# GaggiaBoard_V3.net
KiCad netlist of a schematic drawn in EAGLE
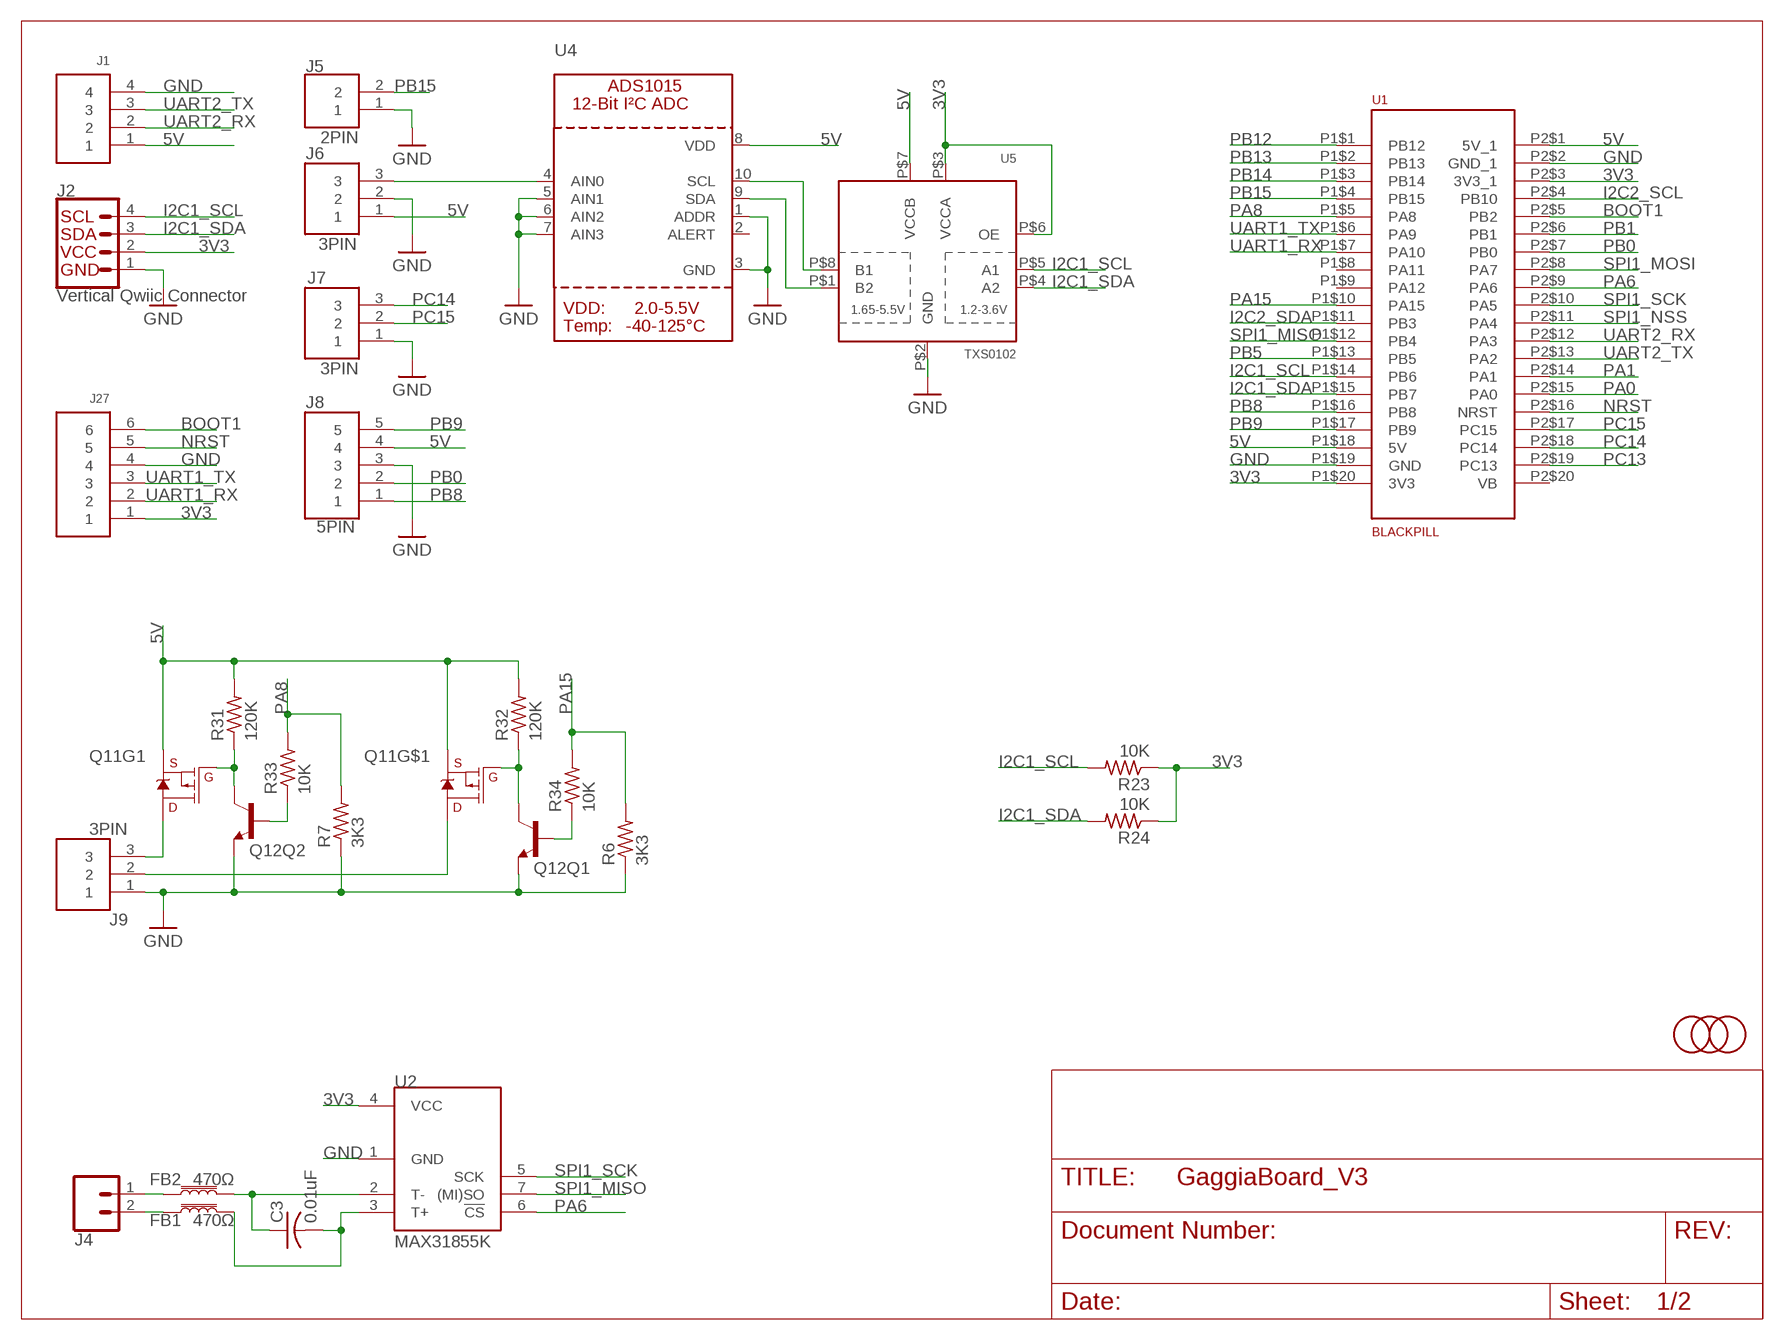
[diagram p0: schematic, sheet 1]
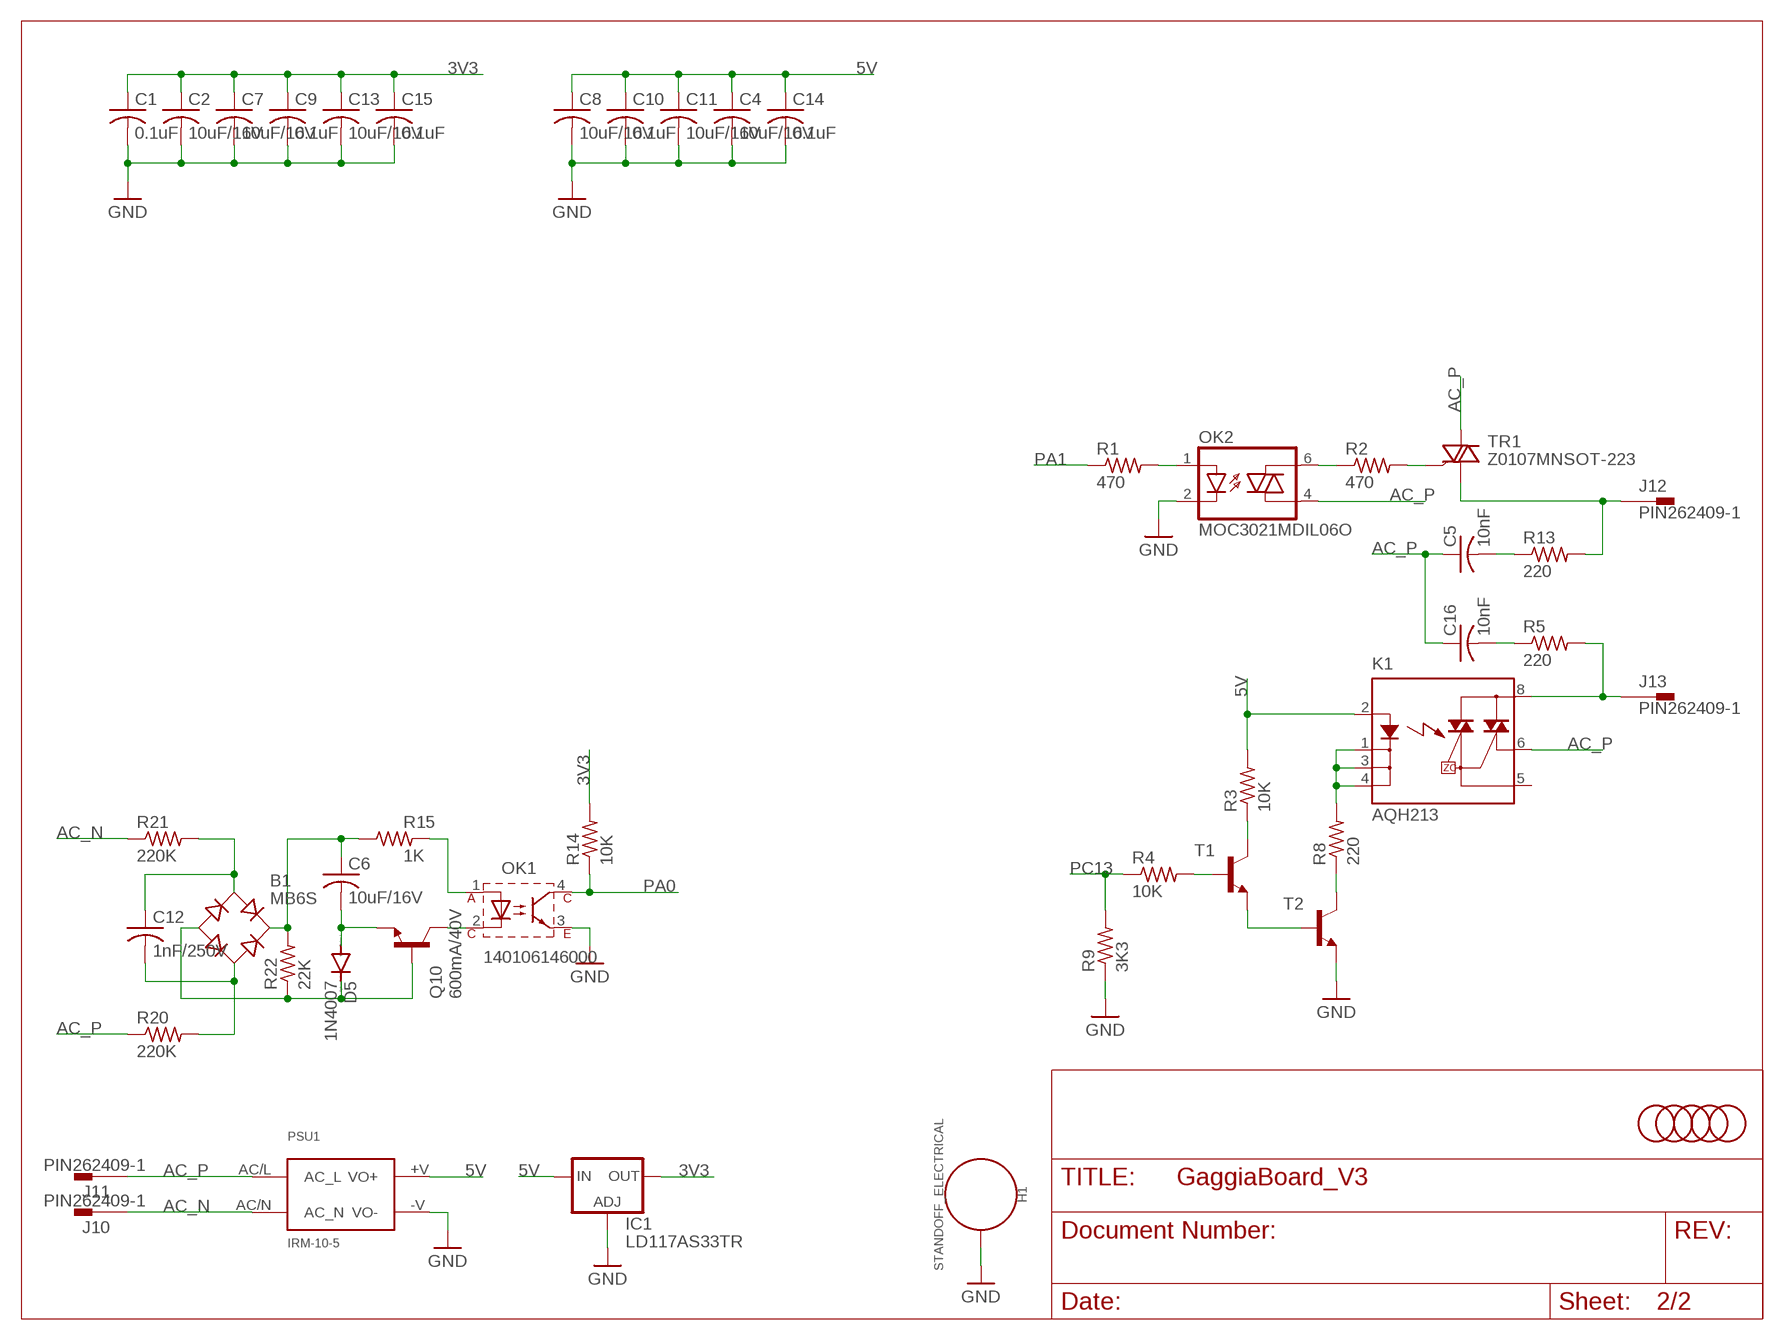
[diagram p1: schematic, sheet 2]

(export (version "E")
  (design (tool "Eeschema 10.0.6"))
  (components
    (comp (ref "B1")
      (value "MB6S")
      (footprint "eagle-import:SOIC-4")
      (libsource (lib "eagle-import") (part "MBS6"))
    )
    (comp (ref "C1")
      (value "0.1uF")
      (footprint "eagle-import:C0603")
      (libsource (lib "eagle-import") (part "C-USC0603"))
    )
    (comp (ref "C2")
      (value "10uF/16V")
      (footprint "eagle-import:C0603")
      (libsource (lib "eagle-import") (part "C-USC0603"))
    )
    (comp (ref "C4")
      (value "10uF/16V")
      (footprint "eagle-import:C0603")
      (libsource (lib "eagle-import") (part "C-USC0603"))
    )
    (comp (ref "C5")
      (value "10nF")
      (footprint "eagle-import:C1206")
      (libsource (lib "eagle-import") (part "C-USC1206"))
    )
    (comp (ref "C6")
      (value "10uF/16V")
      (footprint "eagle-import:C0603")
      (libsource (lib "eagle-import") (part "C-USC0603"))
    )
    (comp (ref "C7")
      (value "10uF/16V")
      (footprint "eagle-import:C0603")
      (libsource (lib "eagle-import") (part "C-USC0603"))
    )
    (comp (ref "C8")
      (value "10uF/16V")
      (footprint "eagle-import:C0603")
      (libsource (lib "eagle-import") (part "C-USC0603"))
    )
    (comp (ref "C9")
      (value "0.1uF")
      (footprint "eagle-import:C0603")
      (libsource (lib "eagle-import") (part "C-USC0603"))
    )
    (comp (ref "C10")
      (value "0.1uF")
      (footprint "eagle-import:C0603")
      (libsource (lib "eagle-import") (part "C-USC0603"))
    )
    (comp (ref "C11")
      (value "10uF/16V")
      (footprint "eagle-import:C0603")
      (libsource (lib "eagle-import") (part "C-USC0603"))
    )
    (comp (ref "C12")
      (value "1nF/250V")
      (footprint "eagle-import:C0603")
      (libsource (lib "eagle-import") (part "C-USC0603"))
    )
    (comp (ref "C13")
      (value "10uF/16V")
      (footprint "eagle-import:C0603")
      (libsource (lib "eagle-import") (part "C-USC0603"))
    )
    (comp (ref "C14")
      (value "0.1uF")
      (footprint "eagle-import:C0603")
      (libsource (lib "eagle-import") (part "C-USC0603"))
    )
    (comp (ref "C15")
      (value "0.1uF")
      (footprint "eagle-import:C0603")
      (libsource (lib "eagle-import") (part "C-USC0603"))
    )
    (comp (ref "C16")
      (value "10nF")
      (footprint "eagle-import:C1206")
      (libsource (lib "eagle-import") (part "C-USC1206"))
    )
    (comp (ref "D5")
      (value "1N4007")
      (footprint "eagle-import:DO214AC")
      (libsource (lib "eagle-import") (part "DIODE-DO214AC"))
    )
    (comp (ref "H1")
      (value "STANDOFF_ELECTRICAL")
      (footprint "eagle-import:STANDOFF-ELECTRICAL")
      (libsource (lib "eagle-import") (part "STANDOFF_ELECTRICAL"))
    )
    (comp (ref "IC1")
      (value "LD117AS33TR")
      (footprint "eagle-import:SOT223")
      (libsource (lib "eagle-import") (part "LD117A?S33TR"))
    )
    (comp (ref "J10")
      (value "PIN262409-1")
      (footprint "eagle-import:62409-1")
      (libsource (lib "eagle-import") (part "PIN262409-1"))
    )
    (comp (ref "J11")
      (value "PIN262409-1")
      (footprint "eagle-import:62409-1")
      (libsource (lib "eagle-import") (part "PIN262409-1"))
    )
    (comp (ref "J12")
      (value "PIN262409-1")
      (footprint "eagle-import:62409-1")
      (libsource (lib "eagle-import") (part "PIN262409-1"))
    )
    (comp (ref "J13")
      (value "PIN262409-1")
      (footprint "eagle-import:62409-1")
      (libsource (lib "eagle-import") (part "PIN262409-1"))
    )
    (comp (ref "K1")
      (value "AQH213")
      (footprint "eagle-import:DIL07")
      (libsource (lib "eagle-import") (part "AQH213"))
    )
    (comp (ref "MARK3")
      (value "FIDUCIAL")
      (footprint "eagle-import:FIDUCIAL_1MM")
      (libsource (lib "eagle-import") (part "FIDUCIAL"))
    )
    (comp (ref "MARK4")
      (value "FIDUCIAL")
      (footprint "eagle-import:FIDUCIAL_1MM")
      (libsource (lib "eagle-import") (part "FIDUCIAL"))
    )
    (comp (ref "MARK6")
      (value "FIDUCIAL")
      (footprint "eagle-import:FIDUCIAL_1MM")
      (libsource (lib "eagle-import") (part "FIDUCIAL"))
    )
    (comp (ref "MARK7")
      (value "FIDUCIAL")
      (footprint "eagle-import:FIDUCIAL_1MM")
      (libsource (lib "eagle-import") (part "FIDUCIAL"))
    )
    (comp (ref "MARK8")
      (value "FIDUCIAL")
      (footprint "eagle-import:FIDUCIAL_1MM")
      (libsource (lib "eagle-import") (part "FIDUCIAL"))
    )
    (comp (ref "OK1")
      (value "140106146000")
      (footprint "eagle-import:WL-OCPT_LSOP4")
      (libsource (lib "eagle-import") (part "WL-OCPT_SERIES_101X_140106146000"))
    )
    (comp (ref "OK2")
      (value "MOC3021MDIL06O")
      (footprint "eagle-import:DIL06O")
      (libsource (lib "eagle-import") (part "MOC3021MDIL06O"))
    )
    (comp (ref "PSU1")
      (value "IRM-10-5")
      (footprint "eagle-import:IRM-10")
      (fields (field (name "SPICEPREFIX") "E"))
      (libsource (lib "eagle-import") (part "IRM-10-5"))
    )
    (comp (ref "Q10")
      (value "600mA/40V")
      (footprint "eagle-import:SOT23-3")
      (libsource (lib "eagle-import") (part "TRANS_NPN-MMBT2222AL"))
    )
    (comp (ref "R1")
      (value "470")
      (footprint "eagle-import:R0603")
      (libsource (lib "eagle-import") (part "R-US_R0603"))
    )
    (comp (ref "R2")
      (value "470")
      (footprint "eagle-import:R0603")
      (libsource (lib "eagle-import") (part "R-US_R0603"))
    )
    (comp (ref "R3")
      (value "10K")
      (footprint "eagle-import:R0603")
      (libsource (lib "eagle-import") (part "R-US_R0603"))
    )
    (comp (ref "R4")
      (value "10K")
      (footprint "eagle-import:R0603")
      (libsource (lib "eagle-import") (part "R-US_R0603"))
    )
    (comp (ref "R5")
      (value "220")
      (footprint "eagle-import:R2512")
      (libsource (lib "eagle-import") (part "R-US_R2512"))
    )
    (comp (ref "R8")
      (value "220")
      (footprint "eagle-import:R0603")
      (libsource (lib "eagle-import") (part "R-US_R0603"))
    )
    (comp (ref "R9")
      (value "3K3")
      (footprint "eagle-import:R0603")
      (libsource (lib "eagle-import") (part "R-US_R0603"))
    )
    (comp (ref "R13")
      (value "220")
      (footprint "eagle-import:R2512")
      (libsource (lib "eagle-import") (part "R-US_R2512"))
    )
    (comp (ref "R14")
      (value "10K")
      (footprint "eagle-import:R0603")
      (libsource (lib "eagle-import") (part "R-US_R0603"))
    )
    (comp (ref "R15")
      (value "1K")
      (footprint "eagle-import:R0603")
      (libsource (lib "eagle-import") (part "R-US_R0603"))
    )
    (comp (ref "R20")
      (value "220K")
      (footprint "eagle-import:R1206")
      (libsource (lib "eagle-import") (part "R-US_R1206"))
    )
    (comp (ref "R21")
      (value "220K")
      (footprint "eagle-import:R1206")
      (libsource (lib "eagle-import") (part "R-US_R1206"))
    )
    (comp (ref "R22")
      (value "22K")
      (footprint "eagle-import:R0603")
      (libsource (lib "eagle-import") (part "R-US_R0603"))
    )
    (comp (ref "T1")
      (value "MMBT2222ALT1-NPN-SOT23-BEC")
      (footprint "eagle-import:SOT23-BEC")
      (libsource (lib "eagle-import") (part "-NPN-SOT23-BECMMBT2222ALT1"))
    )
    (comp (ref "T2")
      (value "MMBT2222ALT1-NPN-SOT23-BEC")
      (footprint "eagle-import:SOT23-BEC")
      (libsource (lib "eagle-import") (part "-NPN-SOT23-BECMMBT2222ALT1"))
    )
    (comp (ref "TR1")
      (value "Z0107MNSOT-223")
      (footprint "eagle-import:SOT223")
      (libsource (lib "eagle-import") (part "Z0107MNSOT-223"))
    )
    (comp (ref "C3")
      (value "0.01uF")
      (footprint "eagle-import:C0603")
      (libsource (lib "eagle-import") (part "C-USC0603"))
    )
    (comp (ref "FB1")
      (value "470Ω")
      (footprint "eagle-import:0603")
      (libsource (lib "eagle-import") (part "FERRITE_BEAD-0603-470Ω-100MHZ-1A-200MILIΩ"))
    )
    (comp (ref "FB2")
      (value "470Ω")
      (footprint "eagle-import:0603")
      (libsource (lib "eagle-import") (part "FERRITE_BEAD-0603-470Ω-100MHZ-1A-200MILIΩ"))
    )
    (comp (ref "J1")
      (value "4PIN")
      (footprint "eagle-import:B4B-PH-K-S")
      (libsource (lib "eagle-import") (part "4PIN"))
    )
    (comp (ref "J2")
      (value "Vertical Qwiic Connector")
      (footprint "eagle-import:JST04_1MM_VERT")
      (libsource (lib "eagle-import") (part "QWIIC_CONNECTOR"))
    )
    (comp (ref "J4")
      (value "CONN_023.5MM-NO_SILK")
      (footprint "eagle-import:SCREWTERMINAL-3.5MM-2-NS")
      (libsource (lib "eagle-import") (part "CONN_023.5MM-NO_SILK"))
    )
    (comp (ref "J5")
      (value "2PIN")
      (footprint "eagle-import:B2B-PH-K-S")
      (libsource (lib "eagle-import") (part "2PIN"))
    )
    (comp (ref "J6")
      (value "3PIN")
      (footprint "eagle-import:B3B-PH-K-S")
      (libsource (lib "eagle-import") (part "3PIN"))
    )
    (comp (ref "J7")
      (value "3PIN")
      (footprint "eagle-import:B3B-PH-K-S")
      (libsource (lib "eagle-import") (part "3PIN"))
    )
    (comp (ref "J8")
      (value "5PIN")
      (footprint "eagle-import:B5B-PH-K-S")
      (libsource (lib "eagle-import") (part "5PIN"))
    )
    (comp (ref "J9")
      (value "3PIN")
      (footprint "eagle-import:B3B-PH-K-S")
      (libsource (lib "eagle-import") (part "3PIN"))
    )
    (comp (ref "J27")
      (value "6PIN")
      (footprint "eagle-import:B6B-PH-K-S")
      (libsource (lib "eagle-import") (part "6PIN"))
    )
    (comp (ref "MARK1")
      (value "FIDUCIAL")
      (footprint "eagle-import:FIDUCIAL_1MM")
      (libsource (lib "eagle-import") (part "FIDUCIAL"))
    )
    (comp (ref "MARK2")
      (value "FIDUCIAL")
      (footprint "eagle-import:FIDUCIAL_1MM")
      (libsource (lib "eagle-import") (part "FIDUCIAL"))
    )
    (comp (ref "MARK5")
      (value "FIDUCIAL")
      (footprint "eagle-import:FIDUCIAL_1MM")
      (libsource (lib "eagle-import") (part "FIDUCIAL"))
    )
    (comp (ref "Q11")
      (value "MOSFET_PCH_DUAL-DMP2240UDM")
      (footprint "eagle-import:SOT26")
      (fields (field (name "LCSC") "C397948"))
      (libsource (lib "eagle-import") (part "MOSFET_PCH_DUAL-DMP2240UDM"))
    )
    (comp (ref "Q12")
      (value "TRANS_NPN_DUAL-MBT3904DW1T1")
      (footprint "eagle-import:SC70-6")
      (fields (field (name "LCSC") "C896759"))
      (libsource (lib "eagle-import") (part "TRANS_NPN_DUAL-MBT3904DW1T1"))
    )
    (comp (ref "R6")
      (value "3K3")
      (footprint "eagle-import:R0603")
      (libsource (lib "eagle-import") (part "R-US_R0603"))
    )
    (comp (ref "R7")
      (value "3K3")
      (footprint "eagle-import:R0603")
      (libsource (lib "eagle-import") (part "R-US_R0603"))
    )
    (comp (ref "R23")
      (value "10K")
      (footprint "eagle-import:R0603")
      (libsource (lib "eagle-import") (part "R-US_R0603"))
    )
    (comp (ref "R24")
      (value "10K")
      (footprint "eagle-import:R0603")
      (libsource (lib "eagle-import") (part "R-US_R0603"))
    )
    (comp (ref "R31")
      (value "120K")
      (footprint "eagle-import:R0603")
      (libsource (lib "eagle-import") (part "R-US_R0603"))
    )
    (comp (ref "R32")
      (value "120K")
      (footprint "eagle-import:R0603")
      (libsource (lib "eagle-import") (part "R-US_R0603"))
    )
    (comp (ref "R33")
      (value "10K")
      (footprint "eagle-import:R0603")
      (libsource (lib "eagle-import") (part "R-US_R0603"))
    )
    (comp (ref "R34")
      (value "10K")
      (footprint "eagle-import:R0603")
      (libsource (lib "eagle-import") (part "R-US_R0603"))
    )
    (comp (ref "U1")
      (value "BLACKPILL")
      (footprint "eagle-import:BLACKPILL")
      (libsource (lib "eagle-import") (part "BLACKPILL"))
    )
    (comp (ref "U2")
      (value "MAX31855K")
      (footprint "eagle-import:SO08")
      (libsource (lib "eagle-import") (part "MAX31855K"))
    )
    (comp (ref "U4")
      (value "ADC_ADS1015")
      (footprint "eagle-import:MSOP10")
      (libsource (lib "eagle-import") (part "ADC_ADS1015"))
    )
    (comp (ref "U5")
      (value "TXS0102")
      (footprint "eagle-import:VFSOP-8")
      (libsource (lib "eagle-import") (part "TXS0102"))
    )
  )
  (nets
    (net (code "1") (name "3V3") (class "Default")
      (node (ref "C1") (pin "1") (pinfunction "1_1") (pintype "passive"))
      (node (ref "C13") (pin "1") (pinfunction "1_1") (pintype "passive"))
      (node (ref "C15") (pin "1") (pinfunction "1_1") (pintype "passive"))
      (node (ref "C2") (pin "1") (pinfunction "1_1") (pintype "passive"))
      (node (ref "C7") (pin "1") (pinfunction "1_1") (pintype "passive"))
      (node (ref "C9") (pin "1") (pinfunction "1_1") (pintype "passive"))
      (node (ref "IC1") (pin "4") (pinfunction "OUT_4") (pintype "passive"))
      (node (ref "J2") (pin "2") (pinfunction "2_2") (pintype "power_in"))
      (node (ref "J27") (pin "1") (pinfunction "1_1") (pintype "bidirectional"))
      (node (ref "R14") (pin "2") (pinfunction "2_2") (pintype "passive"))
      (node (ref "R23") (pin "1") (pinfunction "1_1") (pintype "passive"))
      (node (ref "R24") (pin "1") (pinfunction "1_1") (pintype "passive"))
      (node (ref "U1") (pin "P1$20") (pinfunction "3V3_P1$20") (pintype "power_in"))
      (node (ref "U1") (pin "P2$3") (pinfunction "3V3_1_P2$3") (pintype "power_in"))
      (node (ref "U2") (pin "4") (pinfunction "VCC_4") (pintype "bidirectional"))
      (node (ref "U5") (pin "P$3") (pinfunction "VCCA_P$3") (pintype "bidirectional"))
      (node (ref "U5") (pin "P$6") (pinfunction "OE_P$6") (pintype "bidirectional"))
    )
    (net (code "2") (name "5V") (class "Default")
      (node (ref "C10") (pin "1") (pinfunction "1_1") (pintype "passive"))
      (node (ref "C11") (pin "1") (pinfunction "1_1") (pintype "passive"))
      (node (ref "C14") (pin "1") (pinfunction "1_1") (pintype "passive"))
      (node (ref "C4") (pin "1") (pinfunction "1_1") (pintype "passive"))
      (node (ref "C8") (pin "1") (pinfunction "1_1") (pintype "passive"))
      (node (ref "IC1") (pin "3") (pinfunction "IN_3") (pintype "input"))
      (node (ref "J1") (pin "1") (pinfunction "1_1") (pintype "bidirectional"))
      (node (ref "J6") (pin "1") (pinfunction "1_1") (pintype "bidirectional"))
      (node (ref "J8") (pin "4") (pinfunction "4_4") (pintype "bidirectional"))
      (node (ref "K1") (pin "2") (pinfunction "A_2") (pintype "passive"))
      (node (ref "PSU1") (pin "+V") (pinfunction "VO+_+V") (pintype "bidirectional"))
      (node (ref "Q11") (pin "S1") (pinfunction "S_S1") (pintype "bidirectional"))
      (node (ref "Q11") (pin "S2") (pinfunction "S_S2") (pintype "bidirectional"))
      (node (ref "R3") (pin "2") (pinfunction "2_2") (pintype "passive"))
      (node (ref "R31") (pin "2") (pinfunction "2_2") (pintype "passive"))
      (node (ref "R32") (pin "2") (pinfunction "2_2") (pintype "passive"))
      (node (ref "U1") (pin "P1$18") (pinfunction "5V_P1$18") (pintype "power_in"))
      (node (ref "U1") (pin "P2$1") (pinfunction "5V_1_P2$1") (pintype "power_in"))
      (node (ref "U4") (pin "8") (pinfunction "VDD_8") (pintype "bidirectional"))
      (node (ref "U5") (pin "P$7") (pinfunction "VCCB_P$7") (pintype "bidirectional"))
    )
    (net (code "3") (name "AC_N") (class "Default")
      (node (ref "J10") (pin "A1") (pinfunction "1_A1") (pintype "passive"))
      (node (ref "J10") (pin "A2") (pinfunction "1_A2") (pintype "passive"))
      (node (ref "PSU1") (pin "AC/N") (pinfunction "AC_N_AC/N") (pintype "bidirectional"))
      (node (ref "R21") (pin "1") (pinfunction "1_1") (pintype "passive"))
    )
    (net (code "4") (name "AC_P") (class "Default")
      (node (ref "C16") (pin "1") (pinfunction "1_1") (pintype "passive"))
      (node (ref "C5") (pin "1") (pinfunction "1_1") (pintype "passive"))
      (node (ref "J11") (pin "A1") (pinfunction "1_A1") (pintype "passive"))
      (node (ref "J11") (pin "A2") (pinfunction "1_A2") (pintype "passive"))
      (node (ref "K1") (pin "6") (pinfunction "DS3_6") (pintype "passive"))
      (node (ref "OK2") (pin "4") (pinfunction "A1_4") (pintype "passive"))
      (node (ref "PSU1") (pin "AC/L") (pinfunction "AC_L_AC/L") (pintype "bidirectional"))
      (node (ref "R20") (pin "1") (pinfunction "1_1") (pintype "passive"))
      (node (ref "TR1") (pin "2") (pinfunction "A2_2") (pintype "passive"))
      (node (ref "TR1") (pin "4") (pinfunction "A2_4") (pintype "passive"))
    )
    (net (code "5") (name "BOOT1") (class "Default")
      (node (ref "J27") (pin "6") (pinfunction "6_6") (pintype "bidirectional"))
      (node (ref "U1") (pin "P2$5") (pinfunction "PB2_P2$5") (pintype "bidirectional"))
    )
    (net (code "6") (name "GND") (class "Default")
      (node (ref "C1") (pin "2") (pinfunction "2_2") (pintype "passive"))
      (node (ref "C10") (pin "2") (pinfunction "2_2") (pintype "passive"))
      (node (ref "C11") (pin "2") (pinfunction "2_2") (pintype "passive"))
      (node (ref "C13") (pin "2") (pinfunction "2_2") (pintype "passive"))
      (node (ref "C14") (pin "2") (pinfunction "2_2") (pintype "passive"))
      (node (ref "C15") (pin "2") (pinfunction "2_2") (pintype "passive"))
      (node (ref "C2") (pin "2") (pinfunction "2_2") (pintype "passive"))
      (node (ref "C4") (pin "2") (pinfunction "2_2") (pintype "passive"))
      (node (ref "C7") (pin "2") (pinfunction "2_2") (pintype "passive"))
      (node (ref "C8") (pin "2") (pinfunction "2_2") (pintype "passive"))
      (node (ref "C9") (pin "2") (pinfunction "2_2") (pintype "passive"))
      (node (ref "H1") (pin "P1") (pinfunction "P$1_P1") (pintype "bidirectional"))
      (node (ref "IC1") (pin "1") (pinfunction "ADJ_1") (pintype "input"))
      (node (ref "J1") (pin "4") (pinfunction "4_4") (pintype "bidirectional"))
      (node (ref "J2") (pin "1") (pinfunction "1_1") (pintype "power_in"))
      (node (ref "J27") (pin "4") (pinfunction "4_4") (pintype "bidirectional"))
      (node (ref "J5") (pin "1") (pinfunction "1_1") (pintype "bidirectional"))
      (node (ref "J6") (pin "2") (pinfunction "2_2") (pintype "bidirectional"))
      (node (ref "J7") (pin "1") (pinfunction "1_1") (pintype "bidirectional"))
      (node (ref "J8") (pin "3") (pinfunction "3_3") (pintype "bidirectional"))
      (node (ref "J9") (pin "1") (pinfunction "1_1") (pintype "bidirectional"))
      (node (ref "OK1") (pin "3") (pinfunction "3_3") (pintype "passive"))
      (node (ref "OK2") (pin "2") (pinfunction "C_2") (pintype "passive"))
      (node (ref "PSU1") (pin "-V") (pinfunction "VO-_-V") (pintype "bidirectional"))
      (node (ref "Q12") (pin "1") (pinfunction "E_1") (pintype "passive"))
      (node (ref "Q12") (pin "4") (pinfunction "E_4") (pintype "passive"))
      (node (ref "R6") (pin "1") (pinfunction "1_1") (pintype "passive"))
      (node (ref "R7") (pin "1") (pinfunction "1_1") (pintype "passive"))
      (node (ref "R9") (pin "1") (pinfunction "1_1") (pintype "passive"))
      (node (ref "T2") (pin "E") (pinfunction "E_E") (pintype "passive"))
      (node (ref "U1") (pin "P1$19") (pinfunction "GND_P1$19") (pintype "power_in"))
      (node (ref "U1") (pin "P2$2") (pinfunction "GND_1_P2$2") (pintype "power_in"))
      (node (ref "U2") (pin "1") (pinfunction "GND_1") (pintype "bidirectional"))
      (node (ref "U4") (pin "1") (pinfunction "ADDR_1") (pintype "bidirectional"))
      (node (ref "U4") (pin "3") (pinfunction "GND_3") (pintype "bidirectional"))
      (node (ref "U4") (pin "5") (pinfunction "AIN1_5") (pintype "bidirectional"))
      (node (ref "U4") (pin "6") (pinfunction "AIN2_6") (pintype "bidirectional"))
      (node (ref "U4") (pin "7") (pinfunction "AIN3_7") (pintype "bidirectional"))
      (node (ref "U5") (pin "P$2") (pinfunction "GND_P$2") (pintype "bidirectional"))
    )
    (net (code "7") (name "I2C1_SCL") (class "Default")
      (node (ref "J2") (pin "4") (pinfunction "4_4") (pintype "passive"))
      (node (ref "R23") (pin "2") (pinfunction "2_2") (pintype "passive"))
      (node (ref "U1") (pin "P1$14") (pinfunction "PB6_P1$14") (pintype "bidirectional"))
      (node (ref "U5") (pin "P$5") (pinfunction "A1_P$5") (pintype "bidirectional"))
    )
    (net (code "8") (name "I2C1_SDA") (class "Default")
      (node (ref "J2") (pin "3") (pinfunction "3_3") (pintype "passive"))
      (node (ref "R24") (pin "2") (pinfunction "2_2") (pintype "passive"))
      (node (ref "U1") (pin "P1$15") (pinfunction "PB7_P1$15") (pintype "bidirectional"))
      (node (ref "U5") (pin "P$4") (pinfunction "A2_P$4") (pintype "bidirectional"))
    )
    (net (code "9") (name "I2C2_SCL") (class "Default")
      (node (ref "U1") (pin "P2$4") (pinfunction "PB10_P2$4") (pintype "bidirectional"))
    )
    (net (code "10") (name "I2C2_SDA") (class "Default")
      (node (ref "U1") (pin "P1$11") (pinfunction "PB3_P1$11") (pintype "bidirectional"))
    )
    (net (code "11") (name "NRST") (class "Default")
      (node (ref "J27") (pin "5") (pinfunction "5_5") (pintype "bidirectional"))
      (node (ref "U1") (pin "P2$16") (pinfunction "NRST_P2$16") (pintype "bidirectional"))
    )
    (net (code "12") (name "Net-(B1-AC1)") (class "Default")
      (node (ref "B1") (pin "~1") (pinfunction "AC1_~1") (pintype "passive"))
      (node (ref "C12") (pin "2") (pinfunction "2_2") (pintype "passive"))
      (node (ref "R20") (pin "2") (pinfunction "2_2") (pintype "passive"))
    )
    (net (code "13") (name "Net-(B1-AC2)") (class "Default")
      (node (ref "B1") (pin "~2") (pinfunction "AC2_~2") (pintype "passive"))
      (node (ref "C12") (pin "1") (pinfunction "1_1") (pintype "passive"))
      (node (ref "R21") (pin "2") (pinfunction "2_2") (pintype "passive"))
    )
    (net (code "14") (name "Net-(B1-Pad+)") (class "Default")
      (node (ref "B1") (pin "+") (pinfunction "+_+") (pintype "passive"))
      (node (ref "C6") (pin "1") (pinfunction "1_1") (pintype "passive"))
      (node (ref "R15") (pin "1") (pinfunction "1_1") (pintype "passive"))
      (node (ref "R22") (pin "2") (pinfunction "2_2") (pintype "passive"))
    )
    (net (code "15") (name "Net-(C5-Pad2)") (class "Default")
      (node (ref "C5") (pin "2") (pinfunction "2_2") (pintype "passive"))
      (node (ref "R13") (pin "1") (pinfunction "1_1") (pintype "passive"))
    )
    (net (code "16") (name "Net-(C16-Pad2)") (class "Default")
      (node (ref "C16") (pin "2") (pinfunction "2_2") (pintype "passive"))
      (node (ref "R5") (pin "1") (pinfunction "1_1") (pintype "passive"))
    )
    (net (code "17") (name "Net-(FB1-Pad1)") (class "Default")
      (node (ref "FB1") (pin "1") (pinfunction "1_1") (pintype "passive"))
      (node (ref "J4") (pin "2") (pinfunction "2_2") (pintype "passive"))
    )
    (net (code "18") (name "Net-(FB2-Pad1)") (class "Default")
      (node (ref "FB2") (pin "1") (pinfunction "1_1") (pintype "passive"))
      (node (ref "J4") (pin "1") (pinfunction "1_1") (pintype "passive"))
    )
    (net (code "19") (name "Net-(K1-DS1)") (class "Default")
      (node (ref "J13") (pin "A1") (pinfunction "1_A1") (pintype "passive"))
      (node (ref "J13") (pin "A2") (pinfunction "1_A2") (pintype "passive"))
      (node (ref "K1") (pin "8") (pinfunction "DS1_8") (pintype "passive"))
      (node (ref "R5") (pin "2") (pinfunction "2_2") (pintype "passive"))
    )
    (net (code "20") (name "Net-(K1-K)") (class "Default")
      (node (ref "K1") (pin "1") (pinfunction "K_1") (pintype "passive"))
      (node (ref "K1") (pin "3") (pinfunction "K1_3") (pintype "passive"))
      (node (ref "K1") (pin "4") (pinfunction "K2_4") (pintype "passive"))
      (node (ref "R8") (pin "2") (pinfunction "2_2") (pintype "passive"))
    )
    (net (code "21") (name "Net-(OK1-Pad1)") (class "Default")
      (node (ref "OK1") (pin "1") (pinfunction "1_1") (pintype "passive"))
      (node (ref "R15") (pin "2") (pinfunction "2_2") (pintype "passive"))
    )
    (net (code "22") (name "Net-(OK2-A)") (class "Default")
      (node (ref "OK2") (pin "1") (pinfunction "A_1") (pintype "passive"))
      (node (ref "R1") (pin "2") (pinfunction "2_2") (pintype "passive"))
    )
    (net (code "23") (name "Net-(OK2-A2)") (class "Default")
      (node (ref "OK2") (pin "6") (pinfunction "A2_6") (pintype "passive"))
      (node (ref "R2") (pin "1") (pinfunction "1_1") (pintype "passive"))
    )
    (net (code "24") (name "Net-(Q10-B)") (class "Default")
      (node (ref "B1") (pin "-") (pinfunction "-_-") (pintype "passive"))
      (node (ref "D5") (pin "C") (pinfunction "C_C") (pintype "passive"))
      (node (ref "Q10") (pin "1") (pinfunction "B_1") (pintype "passive"))
      (node (ref "R22") (pin "1") (pinfunction "1_1") (pintype "passive"))
    )
    (net (code "25") (name "Net-(Q10-C)") (class "Default")
      (node (ref "OK1") (pin "2") (pinfunction "2_2") (pintype "passive"))
      (node (ref "Q10") (pin "3") (pinfunction "C_3") (pintype "passive"))
    )
    (net (code "26") (name "Net-(Q10-E)") (class "Default")
      (node (ref "C6") (pin "2") (pinfunction "2_2") (pintype "passive"))
      (node (ref "D5") (pin "A") (pinfunction "A_A") (pintype "passive"))
      (node (ref "Q10") (pin "2") (pinfunction "E_2") (pintype "passive"))
    )
    (net (code "27") (name "Net-(Q11A-D)") (class "Default")
      (node (ref "J9") (pin "2") (pinfunction "2_2") (pintype "bidirectional"))
      (node (ref "Q11") (pin "D2") (pinfunction "D_D2") (pintype "bidirectional"))
    )
    (net (code "28") (name "Net-(Q11A-G)") (class "Default")
      (node (ref "Q11") (pin "G2") (pinfunction "G_G2") (pintype "bidirectional"))
      (node (ref "Q12") (pin "3") (pinfunction "C_3") (pintype "passive"))
      (node (ref "R32") (pin "1") (pinfunction "1_1") (pintype "passive"))
    )
    (net (code "29") (name "Net-(Q11B-D)") (class "Default")
      (node (ref "J9") (pin "3") (pinfunction "3_3") (pintype "bidirectional"))
      (node (ref "Q11") (pin "D1") (pinfunction "D_D1") (pintype "bidirectional"))
    )
    (net (code "30") (name "Net-(Q11B-G)") (class "Default")
      (node (ref "Q11") (pin "G1") (pinfunction "G_G1") (pintype "bidirectional"))
      (node (ref "Q12") (pin "6") (pinfunction "C_6") (pintype "passive"))
      (node (ref "R31") (pin "1") (pinfunction "1_1") (pintype "passive"))
    )
    (net (code "31") (name "Net-(Q12A-B)") (class "Default")
      (node (ref "Q12") (pin "5") (pinfunction "B_5") (pintype "passive"))
      (node (ref "R34") (pin "1") (pinfunction "1_1") (pintype "passive"))
    )
    (net (code "32") (name "Net-(Q12B-B)") (class "Default")
      (node (ref "Q12") (pin "2") (pinfunction "B_2") (pintype "passive"))
      (node (ref "R33") (pin "1") (pinfunction "1_1") (pintype "passive"))
    )
    (net (code "33") (name "Net-(R3-Pad1)") (class "Default")
      (node (ref "R3") (pin "1") (pinfunction "1_1") (pintype "passive"))
      (node (ref "T1") (pin "C") (pinfunction "C_C") (pintype "passive"))
    )
    (net (code "34") (name "Net-(R4-Pad2)") (class "Default")
      (node (ref "R4") (pin "2") (pinfunction "2_2") (pintype "passive"))
      (node (ref "T1") (pin "B") (pinfunction "B_B") (pintype "passive"))
    )
    (net (code "35") (name "Net-(R8-Pad1)") (class "Default")
      (node (ref "R8") (pin "1") (pinfunction "1_1") (pintype "passive"))
      (node (ref "T2") (pin "C") (pinfunction "C_C") (pintype "passive"))
    )
    (net (code "36") (name "Net-(T1-PadE)") (class "Default")
      (node (ref "T1") (pin "E") (pinfunction "E_E") (pintype "passive"))
      (node (ref "T2") (pin "B") (pinfunction "B_B") (pintype "passive"))
    )
    (net (code "37") (name "Net-(TR1-A1)") (class "Default")
      (node (ref "J12") (pin "A1") (pinfunction "1_A1") (pintype "passive"))
      (node (ref "J12") (pin "A2") (pinfunction "1_A2") (pintype "passive"))
      (node (ref "R13") (pin "2") (pinfunction "2_2") (pintype "passive"))
      (node (ref "TR1") (pin "1") (pinfunction "A1_1") (pintype "passive"))
    )
    (net (code "38") (name "Net-(TR1-G)") (class "Default")
      (node (ref "R2") (pin "2") (pinfunction "2_2") (pintype "passive"))
      (node (ref "TR1") (pin "3") (pinfunction "G_3") (pintype "passive"))
    )
    (net (code "39") (name "Net-(U2-T+)") (class "Default")
      (node (ref "C3") (pin "2") (pinfunction "2_2") (pintype "passive"))
      (node (ref "FB1") (pin "2") (pinfunction "2_2") (pintype "passive"))
      (node (ref "U2") (pin "3") (pinfunction "T+_3") (pintype "bidirectional"))
    )
    (net (code "40") (name "Net-(U2-T-)") (class "Default")
      (node (ref "C3") (pin "1") (pinfunction "1_1") (pintype "passive"))
      (node (ref "FB2") (pin "2") (pinfunction "2_2") (pintype "passive"))
      (node (ref "U2") (pin "2") (pinfunction "T-_2") (pintype "bidirectional"))
    )
    (net (code "41") (name "Net-(U4-AIN0)") (class "Default")
      (node (ref "J6") (pin "3") (pinfunction "3_3") (pintype "bidirectional"))
      (node (ref "U4") (pin "4") (pinfunction "AIN0_4") (pintype "bidirectional"))
    )
    (net (code "42") (name "Net-(U4-SCL)") (class "Default")
      (node (ref "U4") (pin "10") (pinfunction "SCL_10") (pintype "bidirectional"))
      (node (ref "U5") (pin "P$8") (pinfunction "B1_P$8") (pintype "bidirectional"))
    )
    (net (code "43") (name "Net-(U4-SDA)") (class "Default")
      (node (ref "U4") (pin "9") (pinfunction "SDA_9") (pintype "bidirectional"))
      (node (ref "U5") (pin "P$1") (pinfunction "B2_P$1") (pintype "bidirectional"))
    )
    (net (code "44") (name "PA0") (class "Default")
      (node (ref "OK1") (pin "4") (pinfunction "4_4") (pintype "passive"))
      (node (ref "R14") (pin "1") (pinfunction "1_1") (pintype "passive"))
      (node (ref "U1") (pin "P2$15") (pinfunction "PA0_P2$15") (pintype "bidirectional"))
    )
    (net (code "45") (name "PA1") (class "Default")
      (node (ref "R1") (pin "1") (pinfunction "1_1") (pintype "passive"))
      (node (ref "U1") (pin "P2$14") (pinfunction "PA1_P2$14") (pintype "bidirectional"))
    )
    (net (code "46") (name "PA6") (class "Default")
      (node (ref "U1") (pin "P2$9") (pinfunction "PA6_P2$9") (pintype "bidirectional"))
      (node (ref "U2") (pin "6") (pinfunction "~{CS}_6") (pintype "bidirectional"))
    )
    (net (code "47") (name "PA8") (class "Default")
      (node (ref "R33") (pin "2") (pinfunction "2_2") (pintype "passive"))
      (node (ref "R7") (pin "2") (pinfunction "2_2") (pintype "passive"))
      (node (ref "U1") (pin "P1$5") (pinfunction "PA8_P1$5") (pintype "bidirectional"))
    )
    (net (code "48") (name "PA15") (class "Default")
      (node (ref "R34") (pin "2") (pinfunction "2_2") (pintype "passive"))
      (node (ref "R6") (pin "2") (pinfunction "2_2") (pintype "passive"))
      (node (ref "U1") (pin "P1$10") (pinfunction "PA15_P1$10") (pintype "bidirectional"))
    )
    (net (code "49") (name "PB0") (class "Default")
      (node (ref "J8") (pin "2") (pinfunction "2_2") (pintype "bidirectional"))
      (node (ref "U1") (pin "P2$7") (pinfunction "PB0_P2$7") (pintype "bidirectional"))
    )
    (net (code "50") (name "PB1") (class "Default")
      (node (ref "U1") (pin "P2$6") (pinfunction "PB1_P2$6") (pintype "bidirectional"))
    )
    (net (code "51") (name "PB5") (class "Default")
      (node (ref "U1") (pin "P1$13") (pinfunction "PB5_P1$13") (pintype "bidirectional"))
    )
    (net (code "52") (name "PB8") (class "Default")
      (node (ref "J8") (pin "1") (pinfunction "1_1") (pintype "bidirectional"))
      (node (ref "U1") (pin "P1$16") (pinfunction "PB8_P1$16") (pintype "bidirectional"))
    )
    (net (code "53") (name "PB9") (class "Default")
      (node (ref "J8") (pin "5") (pinfunction "5_5") (pintype "bidirectional"))
      (node (ref "U1") (pin "P1$17") (pinfunction "PB9_P1$17") (pintype "bidirectional"))
    )
    (net (code "54") (name "PB12") (class "Default")
      (node (ref "U1") (pin "P1$1") (pinfunction "PB12_P1$1") (pintype "bidirectional"))
    )
    (net (code "55") (name "PB13") (class "Default")
      (node (ref "U1") (pin "P1$2") (pinfunction "PB13_P1$2") (pintype "bidirectional"))
    )
    (net (code "56") (name "PB14") (class "Default")
      (node (ref "U1") (pin "P1$3") (pinfunction "PB14_P1$3") (pintype "bidirectional"))
    )
    (net (code "57") (name "PB15") (class "Default")
      (node (ref "J5") (pin "2") (pinfunction "2_2") (pintype "bidirectional"))
      (node (ref "U1") (pin "P1$4") (pinfunction "PB15_P1$4") (pintype "bidirectional"))
    )
    (net (code "58") (name "PC13") (class "Default")
      (node (ref "R4") (pin "1") (pinfunction "1_1") (pintype "passive"))
      (node (ref "R9") (pin "2") (pinfunction "2_2") (pintype "passive"))
      (node (ref "U1") (pin "P2$19") (pinfunction "PC13_P2$19") (pintype "bidirectional"))
    )
    (net (code "59") (name "PC14") (class "Default")
      (node (ref "J7") (pin "3") (pinfunction "3_3") (pintype "bidirectional"))
      (node (ref "U1") (pin "P2$18") (pinfunction "PC14_P2$18") (pintype "bidirectional"))
    )
    (net (code "60") (name "PC15") (class "Default")
      (node (ref "J7") (pin "2") (pinfunction "2_2") (pintype "bidirectional"))
      (node (ref "U1") (pin "P2$17") (pinfunction "PC15_P2$17") (pintype "bidirectional"))
    )
    (net (code "61") (name "SPI1_MISO") (class "Default")
      (node (ref "U1") (pin "P1$12") (pinfunction "PB4_P1$12") (pintype "bidirectional"))
      (node (ref "U2") (pin "7") (pinfunction "(MI)SO_7") (pintype "bidirectional"))
    )
    (net (code "62") (name "SPI1_MOSI") (class "Default")
      (node (ref "U1") (pin "P2$8") (pinfunction "PA7_P2$8") (pintype "bidirectional"))
    )
    (net (code "63") (name "SPI1_NSS") (class "Default")
      (node (ref "U1") (pin "P2$11") (pinfunction "PA4_P2$11") (pintype "bidirectional"))
    )
    (net (code "64") (name "SPI1_SCK") (class "Default")
      (node (ref "U1") (pin "P2$10") (pinfunction "PA5_P2$10") (pintype "bidirectional"))
      (node (ref "U2") (pin "5") (pinfunction "SCK_5") (pintype "bidirectional"))
    )
    (net (code "65") (name "UART1_RX") (class "Default")
      (node (ref "J27") (pin "2") (pinfunction "2_2") (pintype "bidirectional"))
      (node (ref "U1") (pin "P1$7") (pinfunction "PA10_P1$7") (pintype "bidirectional"))
    )
    (net (code "66") (name "UART1_TX") (class "Default")
      (node (ref "J27") (pin "3") (pinfunction "3_3") (pintype "bidirectional"))
      (node (ref "U1") (pin "P1$6") (pinfunction "PA9_P1$6") (pintype "bidirectional"))
    )
    (net (code "67") (name "UART2_RX") (class "Default")
      (node (ref "J1") (pin "2") (pinfunction "2_2") (pintype "bidirectional"))
      (node (ref "U1") (pin "P2$12") (pinfunction "PA3_P2$12") (pintype "bidirectional"))
    )
    (net (code "68") (name "UART2_TX") (class "Default")
      (node (ref "J1") (pin "3") (pinfunction "3_3") (pintype "bidirectional"))
      (node (ref "U1") (pin "P2$13") (pinfunction "PA2_P2$13") (pintype "bidirectional"))
    )
    (net (code "69") (name "unconnected-(K1-DS2-Pad5)") (class "Default")
      (node (ref "K1") (pin "5") (pinfunction "DS2_5") (pintype "passive"))
    )
    (net (code "70") (name "unconnected-(U1-PA11-PadP1$8)") (class "Default")
      (node (ref "U1") (pin "P1$8") (pinfunction "PA11_P1$8") (pintype "bidirectional"))
    )
    (net (code "71") (name "unconnected-(U1-PA12-PadP1$9)") (class "Default")
      (node (ref "U1") (pin "P1$9") (pinfunction "PA12_P1$9") (pintype "bidirectional"))
    )
    (net (code "72") (name "unconnected-(U1-VB-PadP2$20)") (class "Default")
      (node (ref "U1") (pin "P2$20") (pinfunction "VB_P2$20") (pintype "bidirectional"))
    )
    (net (code "73") (name "unconnected-(U4-ALERT-Pad2)") (class "Default")
      (node (ref "U4") (pin "2") (pinfunction "ALERT_2") (pintype "bidirectional"))
    )
  )
)
